# Micro.net
KiCad netlist of a schematic drawn in Altium Designer
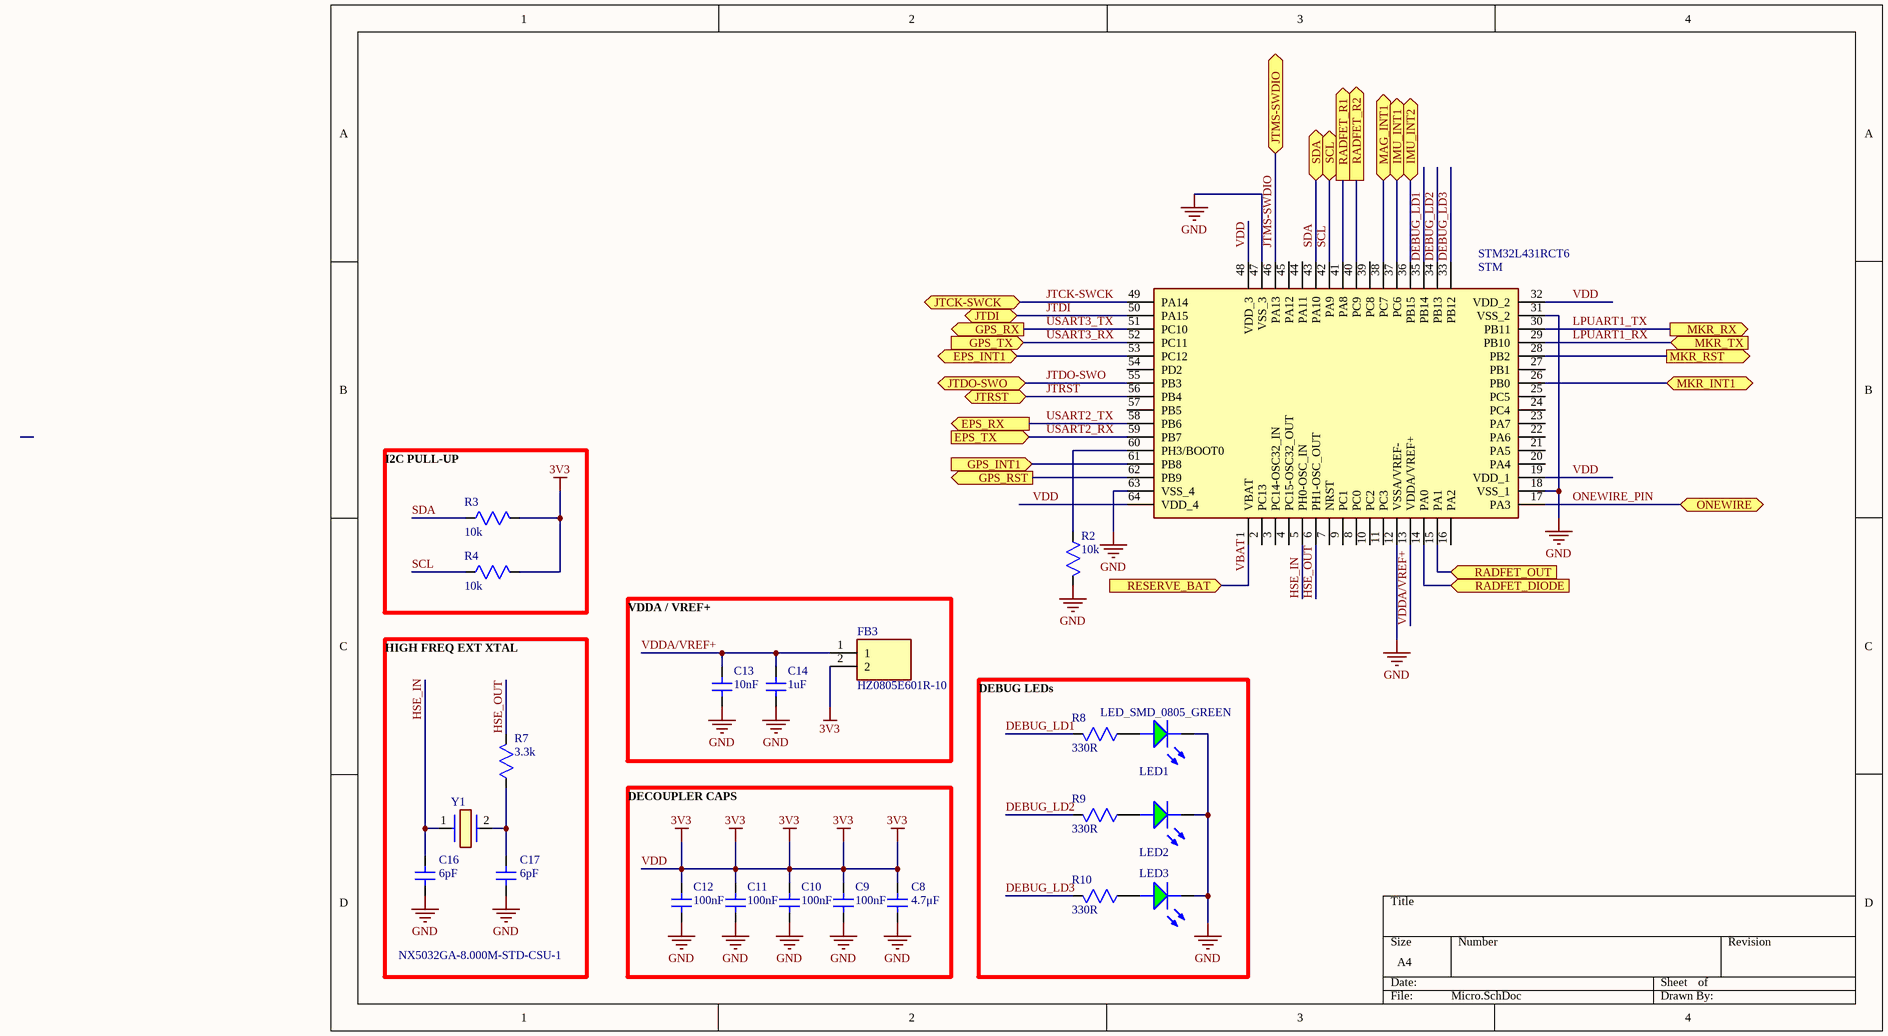
[diagram p0: Micro.SchDoc]

(export (version "E")
  (design (tool "Eeschema 10.0.6"))
  (components
    (comp (ref "C8")
      (value "CAP_0805_4.7uF")
      (footprint "CAP SMD 0805")
      (description "Condensador 0805 4.7uF")
      (fields (field (name "VALOR") "4.7μF"))
      (libsource (lib "ARUS Electronica") (part "Symbol"))
    )
    (comp (ref "C9")
      (value "CAP_0805_100nF")
      (footprint "CAP SMD 0805")
      (description "Condensador 0805 100nF")
      (fields (field (name "VALOR") "100nF"))
      (libsource (lib "ARUS Electronica") (part "CAP_0805_100nF"))
    )
    (comp (ref "C10")
      (value "CAP_0805_100nF")
      (footprint "CAP SMD 0805")
      (description "Condensador 0805 100nF")
      (fields (field (name "VALOR") "100nF"))
      (libsource (lib "ARUS Electronica") (part "CAP_0805_100nF"))
    )
    (comp (ref "C11")
      (value "CAP_0805_100nF")
      (footprint "CAP SMD 0805")
      (description "Condensador 0805 100nF")
      (fields (field (name "VALOR") "100nF"))
      (libsource (lib "ARUS Electronica") (part "CAP_0805_100nF"))
    )
    (comp (ref "C12")
      (value "CAP_0805_100nF")
      (footprint "CAP SMD 0805")
      (description "Condensador 0805 100nF")
      (fields (field (name "VALOR") "100nF"))
      (libsource (lib "ARUS Electronica") (part "CAP_0805_100nF"))
    )
    (comp (ref "C13")
      (value "CAP_0805_100nF")
      (footprint "CAP SMD 0805")
      (description "Condensador 0805 100nF")
      (fields (field (name "VALOR") "10nF"))
      (libsource (lib "ARUS Electronica") (part "CAP_0805_100nF"))
    )
    (comp (ref "C14")
      (value "CAP_0805_100nF")
      (footprint "CAP SMD 0805")
      (description "Condensador 0805 100nF")
      (fields (field (name "VALOR") "1uF"))
      (libsource (lib "ARUS Electronica") (part "CAP_0805_100nF"))
    )
    (comp (ref "C16")
      (value "CAP_0805_4.7uF")
      (footprint "CAP SMD 0805")
      (description "Condensador 0805 4.7uF")
      (fields (field (name "VALOR") "6pF"))
      (libsource (lib "ARUS Electronica") (part "Symbol"))
    )
    (comp (ref "C17")
      (value "CAP_0805_4.7uF")
      (footprint "CAP SMD 0805")
      (description "Condensador 0805 4.7uF")
      (fields (field (name "VALOR") "6pF"))
      (libsource (lib "ARUS Electronica") (part "Symbol"))
    )
    (comp (ref "FB3")
      (value "HZ0805E601R-10")
      (footprint "SamacSys:BEADC2012X110N")
      (description "Ferrite Bead")
      (fields (field (name "MOUSER PART NUMBER") "875-HZ0805E601R-10"))
      (libsource (lib "*") (part "HZ0805E601R-10"))
    )
    (comp (ref "LED1")
      (value "LED_SMD_0805_GREEN")
      (footprint "LED SMD 0805 GREEN")
      (description "LED SMD 0805 GREEN")
      (libsource (lib "ARUS Electronica") (part "LED_SMD_0805_GREEN"))
    )
    (comp (ref "LED2")
      (value "LED_SMD_0805_GREEN")
      (footprint "LED SMD 0805 GREEN")
      (description "LED SMD 0805 GREEN")
      (libsource (lib "ARUS Electronica") (part "LED_SMD_0805_GREEN"))
    )
    (comp (ref "LED3")
      (value "LED_SMD_0805_GREEN")
      (footprint "LED SMD 0805 GREEN")
      (description "LED SMD 0805 GREEN")
      (libsource (lib "ARUS Electronica") (part "LED_SMD_0805_GREEN"))
    )
    (comp (ref "R2")
      (value "RES_0805_10k")
      (footprint "RES SMD 0805")
      (description "Resistencia 0805 10k")
      (fields (field (name "VALOR") "10k"))
      (libsource (lib "ARUS Electronica") (part "RES_2512_22R_2W"))
    )
    (comp (ref "R3")
      (value "RES_0805_10k")
      (footprint "RES SMD 0805")
      (description "Resistencia 0805 10k")
      (fields (field (name "VALOR") "10k"))
      (libsource (lib "ARUS Electronica") (part "RES_2512_22R_2W"))
    )
    (comp (ref "R4")
      (value "RES_0805_10k")
      (footprint "RES SMD 0805")
      (description "Resistencia 0805 10k")
      (fields (field (name "VALOR") "10k"))
      (libsource (lib "ARUS Electronica") (part "RES_2512_22R_2W"))
    )
    (comp (ref "R7")
      (value "RES_0805_10k")
      (footprint "RES SMD 0805")
      (description "Resistencia 0805 10k")
      (fields (field (name "VALOR") "3.3k"))
      (libsource (lib "ARUS Electronica") (part "RES_2512_22R_2W"))
    )
    (comp (ref "R8")
      (value "RES_0805_10k")
      (footprint "RES SMD 0805")
      (description "Resistencia 0805 10k")
      (fields (field (name "VALOR") "330R"))
      (libsource (lib "ARUS Electronica") (part "RES_2512_22R_2W"))
    )
    (comp (ref "R9")
      (value "RES_0805_10k")
      (footprint "RES SMD 0805")
      (description "Resistencia 0805 10k")
      (fields (field (name "VALOR") "330R"))
      (libsource (lib "ARUS Electronica") (part "RES_2512_22R_2W"))
    )
    (comp (ref "R10")
      (value "RES_0805_10k")
      (footprint "RES SMD 0805")
      (description "Resistencia 0805 10k")
      (fields (field (name "VALOR") "330R"))
      (libsource (lib "ARUS Electronica") (part "RES_2512_22R_2W"))
    )
    (comp (ref "STM")
      (value "STM32L431RCT6")
      (footprint "SamacSys:QFP50P1200X1200X160-64N")
      (description "Integrated Circuit")
      (fields (field (name "MOUSER PART NUMBER") "511-STM32L431RCT6"))
      (libsource (lib "*") (part "STM32L431RCT6"))
    )
    (comp (ref "Y1")
      (value "NX5032GA-8.000M-STD-CSU-1")
      (footprint "SamacSys:NX5032GA8000MSTDCSU1")
      (description "Crystal or Oscillator")
      (libsource (lib "*") (part "NX5032GA-8.000M-STD-CSU-1"))
    )
  )
  (nets
    (net (code "1") (name "/DEBUG_LD1") (class "Default")
      (node (ref "R8") (pin "2") (pinfunction "2_2") (pintype "passive"))
      (node (ref "STM") (pin "35") (pinfunction "PB14_35") (pintype "passive"))
    )
    (net (code "2") (name "/DEBUG_LD2") (class "Default")
      (node (ref "R9") (pin "2") (pinfunction "2_2") (pintype "passive"))
      (node (ref "STM") (pin "34") (pinfunction "PB13_34") (pintype "passive"))
    )
    (net (code "3") (name "/DEBUG_LD3") (class "Default")
      (node (ref "R10") (pin "2") (pinfunction "2_2") (pintype "passive"))
      (node (ref "STM") (pin "33") (pinfunction "PB12_33") (pintype "passive"))
    )
    (net (code "4") (name "/EPS_INT1") (class "Default")
      (node (ref "STM") (pin "53") (pinfunction "PC12_53") (pintype "passive"))
    )
    (net (code "5") (name "/GPS_INT1") (class "Default")
      (node (ref "STM") (pin "61") (pinfunction "PB8_61") (pintype "passive"))
    )
    (net (code "6") (name "/GPS_RST") (class "Default")
      (node (ref "STM") (pin "62") (pinfunction "PB9_62") (pintype "passive"))
    )
    (net (code "7") (name "/HSE_IN") (class "Default")
      (node (ref "C16") (pin "1") (pinfunction "1_1") (pintype "passive"))
      (node (ref "STM") (pin "5") (pinfunction "PH0-OSC_IN_5") (pintype "passive"))
      (node (ref "Y1") (pin "1") (pinfunction "1_1") (pintype "passive"))
    )
    (net (code "8") (name "/HSE_OUT") (class "Default")
      (node (ref "R7") (pin "2") (pinfunction "2_2") (pintype "passive"))
      (node (ref "STM") (pin "6") (pinfunction "PH1-OSC_OUT_6") (pintype "passive"))
    )
    (net (code "9") (name "/IMU_INT1") (class "Default")
      (node (ref "STM") (pin "37") (pinfunction "PC6_37") (pintype "passive"))
    )
    (net (code "10") (name "/IMU_INT2") (class "Default")
      (node (ref "STM") (pin "36") (pinfunction "PB15_36") (pintype "passive"))
    )
    (net (code "11") (name "/JTCK-SWCK") (class "Default")
      (node (ref "STM") (pin "49") (pinfunction "PA14_49") (pintype "passive"))
    )
    (net (code "12") (name "/JTDI") (class "Default")
      (node (ref "STM") (pin "50") (pinfunction "PA15_50") (pintype "passive"))
    )
    (net (code "13") (name "/JTDO-SWO") (class "Default")
      (node (ref "STM") (pin "55") (pinfunction "PB3_55") (pintype "passive"))
    )
    (net (code "14") (name "/JTMS-SWDIO") (class "Default")
      (node (ref "STM") (pin "46") (pinfunction "PA13_46") (pintype "passive"))
    )
    (net (code "15") (name "/JTRST") (class "Default")
      (node (ref "STM") (pin "56") (pinfunction "PB4_56") (pintype "passive"))
    )
    (net (code "16") (name "/LPUART1_RX") (class "Default")
      (node (ref "STM") (pin "29") (pinfunction "PB10_29") (pintype "passive"))
    )
    (net (code "17") (name "/LPUART1_TX") (class "Default")
      (node (ref "STM") (pin "30") (pinfunction "PB11_30") (pintype "passive"))
    )
    (net (code "18") (name "/MAG_INT1") (class "Default")
      (node (ref "STM") (pin "38") (pinfunction "PC7_38") (pintype "passive"))
    )
    (net (code "19") (name "/MKR_INT1") (class "Default")
      (node (ref "STM") (pin "26") (pinfunction "PB0_26") (pintype "passive"))
    )
    (net (code "20") (name "/MKR_RST") (class "Default")
      (node (ref "STM") (pin "28") (pinfunction "PB2_28") (pintype "passive"))
    )
    (net (code "21") (name "/ONEWIRE_PIN") (class "Default")
      (node (ref "STM") (pin "17") (pinfunction "PA3_17") (pintype "passive"))
    )
    (net (code "22") (name "/RADFET_DIODE") (class "Default")
      (node (ref "STM") (pin "14") (pinfunction "PA0_14") (pintype "passive"))
    )
    (net (code "23") (name "/RADFET_OUT") (class "Default")
      (node (ref "STM") (pin "15") (pinfunction "PA1_15") (pintype "passive"))
    )
    (net (code "24") (name "/RADFET_R1") (class "Default")
      (node (ref "STM") (pin "41") (pinfunction "PA8_41") (pintype "passive"))
    )
    (net (code "25") (name "/RADFET_R2") (class "Default")
      (node (ref "STM") (pin "40") (pinfunction "PC9_40") (pintype "passive"))
    )
    (net (code "26") (name "/SCL") (class "Default")
      (node (ref "R4") (pin "1") (pinfunction "1_1") (pintype "passive"))
      (node (ref "STM") (pin "42") (pinfunction "PA9_42") (pintype "passive"))
    )
    (net (code "27") (name "/SDA") (class "Default")
      (node (ref "R3") (pin "1") (pinfunction "1_1") (pintype "passive"))
      (node (ref "STM") (pin "43") (pinfunction "PA10_43") (pintype "passive"))
    )
    (net (code "28") (name "/USART2_RX") (class "Default")
      (node (ref "STM") (pin "59") (pinfunction "PB7_59") (pintype "passive"))
    )
    (net (code "29") (name "/USART2_TX") (class "Default")
      (node (ref "STM") (pin "58") (pinfunction "PB6_58") (pintype "passive"))
    )
    (net (code "30") (name "/USART3_RX") (class "Default")
      (node (ref "STM") (pin "52") (pinfunction "PC11_52") (pintype "passive"))
    )
    (net (code "31") (name "/USART3_TX") (class "Default")
      (node (ref "STM") (pin "51") (pinfunction "PC10_51") (pintype "passive"))
    )
    (net (code "32") (name "/VBAT") (class "Default")
      (node (ref "STM") (pin "1") (pinfunction "VBAT_1") (pintype "passive"))
    )
    (net (code "33") (name "/VDDA{slash}VREF+") (class "Default")
      (node (ref "C13") (pin "1") (pinfunction "1_1") (pintype "passive"))
      (node (ref "C14") (pin "1") (pinfunction "1_1") (pintype "passive"))
      (node (ref "FB3") (pin "1") (pinfunction "1_1") (pintype "passive"))
      (node (ref "STM") (pin "13") (pinfunction "VDDA/VREF+_13") (pintype "passive"))
    )
    (net (code "34") (name "3V3") (class "Default")
      (node (ref "C10") (pin "1") (pinfunction "1_1") (pintype "passive"))
      (node (ref "C11") (pin "1") (pinfunction "1_1") (pintype "passive"))
      (node (ref "C12") (pin "1") (pinfunction "1_1") (pintype "passive"))
      (node (ref "C8") (pin "1") (pinfunction "1_1") (pintype "passive"))
      (node (ref "C9") (pin "1") (pinfunction "1_1") (pintype "passive"))
      (node (ref "FB3") (pin "2") (pinfunction "2_2") (pintype "passive"))
      (node (ref "R3") (pin "2") (pinfunction "2_2") (pintype "passive"))
      (node (ref "R4") (pin "2") (pinfunction "2_2") (pintype "passive"))
      (node (ref "STM") (pin "19") (pinfunction "VDD_1_19") (pintype "passive"))
      (node (ref "STM") (pin "32") (pinfunction "VDD_2_32") (pintype "passive"))
      (node (ref "STM") (pin "48") (pinfunction "VDD_3_48") (pintype "passive"))
      (node (ref "STM") (pin "64") (pinfunction "VDD_4_64") (pintype "passive"))
    )
    (net (code "35") (name "GND") (class "Default")
      (node (ref "C10") (pin "2") (pinfunction "2_2") (pintype "passive"))
      (node (ref "C11") (pin "2") (pinfunction "2_2") (pintype "passive"))
      (node (ref "C12") (pin "2") (pinfunction "2_2") (pintype "passive"))
      (node (ref "C13") (pin "2") (pinfunction "2_2") (pintype "passive"))
      (node (ref "C14") (pin "2") (pinfunction "2_2") (pintype "passive"))
      (node (ref "C16") (pin "2") (pinfunction "2_2") (pintype "passive"))
      (node (ref "C17") (pin "2") (pinfunction "2_2") (pintype "passive"))
      (node (ref "C8") (pin "2") (pinfunction "2_2") (pintype "passive"))
      (node (ref "C9") (pin "2") (pinfunction "2_2") (pintype "passive"))
      (node (ref "LED1") (pin "2") (pinfunction "K_2") (pintype "passive"))
      (node (ref "LED2") (pin "2") (pinfunction "K_2") (pintype "passive"))
      (node (ref "LED3") (pin "2") (pinfunction "K_2") (pintype "passive"))
      (node (ref "R2") (pin "2") (pinfunction "2_2") (pintype "passive"))
      (node (ref "STM") (pin "12") (pinfunction "VSSA/VREF-_12") (pintype "passive"))
      (node (ref "STM") (pin "18") (pinfunction "VSS_1_18") (pintype "passive"))
      (node (ref "STM") (pin "31") (pinfunction "VSS_2_31") (pintype "passive"))
      (node (ref "STM") (pin "47") (pinfunction "VSS_3_47") (pintype "passive"))
      (node (ref "STM") (pin "63") (pinfunction "VSS_4_63") (pintype "passive"))
    )
    (net (code "36") (name "Net-(C17-Pad1)") (class "Default")
      (node (ref "C17") (pin "1") (pinfunction "1_1") (pintype "passive"))
      (node (ref "R7") (pin "1") (pinfunction "1_1") (pintype "passive"))
      (node (ref "Y1") (pin "2") (pinfunction "2_2") (pintype "passive"))
    )
    (net (code "37") (name "Net-(LED1-A)") (class "Default")
      (node (ref "LED1") (pin "1") (pinfunction "A_1") (pintype "passive"))
      (node (ref "R8") (pin "1") (pinfunction "1_1") (pintype "passive"))
    )
    (net (code "38") (name "Net-(LED2-A)") (class "Default")
      (node (ref "LED2") (pin "1") (pinfunction "A_1") (pintype "passive"))
      (node (ref "R9") (pin "1") (pinfunction "1_1") (pintype "passive"))
    )
    (net (code "39") (name "Net-(LED3-A)") (class "Default")
      (node (ref "LED3") (pin "1") (pinfunction "A_1") (pintype "passive"))
      (node (ref "R10") (pin "1") (pinfunction "1_1") (pintype "passive"))
    )
    (net (code "40") (name "Net-(STM-PH3{slash}BOOT0)") (class "Default")
      (node (ref "R2") (pin "1") (pinfunction "1_1") (pintype "passive"))
      (node (ref "STM") (pin "60") (pinfunction "PH3/BOOT0_60") (pintype "passive"))
    )
    (net (code "41") (name "unconnected-(STM-NRST-Pad7)") (class "Default")
      (node (ref "STM") (pin "7") (pinfunction "NRST_7") (pintype "passive"))
    )
    (net (code "42") (name "unconnected-(STM-PA2-Pad16)") (class "Default")
      (node (ref "STM") (pin "16") (pinfunction "PA2_16") (pintype "passive"))
    )
    (net (code "43") (name "unconnected-(STM-PA4-Pad20)") (class "Default")
      (node (ref "STM") (pin "20") (pinfunction "PA4_20") (pintype "passive"))
    )
    (net (code "44") (name "unconnected-(STM-PA5-Pad21)") (class "Default")
      (node (ref "STM") (pin "21") (pinfunction "PA5_21") (pintype "passive"))
    )
    (net (code "45") (name "unconnected-(STM-PA6-Pad22)") (class "Default")
      (node (ref "STM") (pin "22") (pinfunction "PA6_22") (pintype "passive"))
    )
    (net (code "46") (name "unconnected-(STM-PA7-Pad23)") (class "Default")
      (node (ref "STM") (pin "23") (pinfunction "PA7_23") (pintype "passive"))
    )
    (net (code "47") (name "unconnected-(STM-PA11-Pad44)") (class "Default")
      (node (ref "STM") (pin "44") (pinfunction "PA11_44") (pintype "passive"))
    )
    (net (code "48") (name "unconnected-(STM-PA12-Pad45)") (class "Default")
      (node (ref "STM") (pin "45") (pinfunction "PA12_45") (pintype "passive"))
    )
    (net (code "49") (name "unconnected-(STM-PB1-Pad27)") (class "Default")
      (node (ref "STM") (pin "27") (pinfunction "PB1_27") (pintype "passive"))
    )
    (net (code "50") (name "unconnected-(STM-PB5-Pad57)") (class "Default")
      (node (ref "STM") (pin "57") (pinfunction "PB5_57") (pintype "passive"))
    )
    (net (code "51") (name "unconnected-(STM-PC0-Pad8)") (class "Default")
      (node (ref "STM") (pin "8") (pinfunction "PC0_8") (pintype "passive"))
    )
    (net (code "52") (name "unconnected-(STM-PC1-Pad9)") (class "Default")
      (node (ref "STM") (pin "9") (pinfunction "PC1_9") (pintype "passive"))
    )
    (net (code "53") (name "unconnected-(STM-PC2-Pad10)") (class "Default")
      (node (ref "STM") (pin "10") (pinfunction "PC2_10") (pintype "passive"))
    )
    (net (code "54") (name "unconnected-(STM-PC3-Pad11)") (class "Default")
      (node (ref "STM") (pin "11") (pinfunction "PC3_11") (pintype "passive"))
    )
    (net (code "55") (name "unconnected-(STM-PC4-Pad24)") (class "Default")
      (node (ref "STM") (pin "24") (pinfunction "PC4_24") (pintype "passive"))
    )
    (net (code "56") (name "unconnected-(STM-PC5-Pad25)") (class "Default")
      (node (ref "STM") (pin "25") (pinfunction "PC5_25") (pintype "passive"))
    )
    (net (code "57") (name "unconnected-(STM-PC8-Pad39)") (class "Default")
      (node (ref "STM") (pin "39") (pinfunction "PC8_39") (pintype "passive"))
    )
    (net (code "58") (name "unconnected-(STM-PC13-Pad2)") (class "Default")
      (node (ref "STM") (pin "2") (pinfunction "PC13_2") (pintype "passive"))
    )
    (net (code "59") (name "unconnected-(STM-PC14-OSC32_IN-Pad3)") (class "Default")
      (node (ref "STM") (pin "3") (pinfunction "PC14-OSC32_IN_3") (pintype "passive"))
    )
    (net (code "60") (name "unconnected-(STM-PC15-OSC32_OUT-Pad4)") (class "Default")
      (node (ref "STM") (pin "4") (pinfunction "PC15-OSC32_OUT_4") (pintype "passive"))
    )
    (net (code "61") (name "unconnected-(STM-PD2-Pad54)") (class "Default")
      (node (ref "STM") (pin "54") (pinfunction "PD2_54") (pintype "passive"))
    )
  )
)
